# TEXAS_INSTRUMENTS_DRV8833.net
KiCad netlist of a schematic drawn in EAGLE
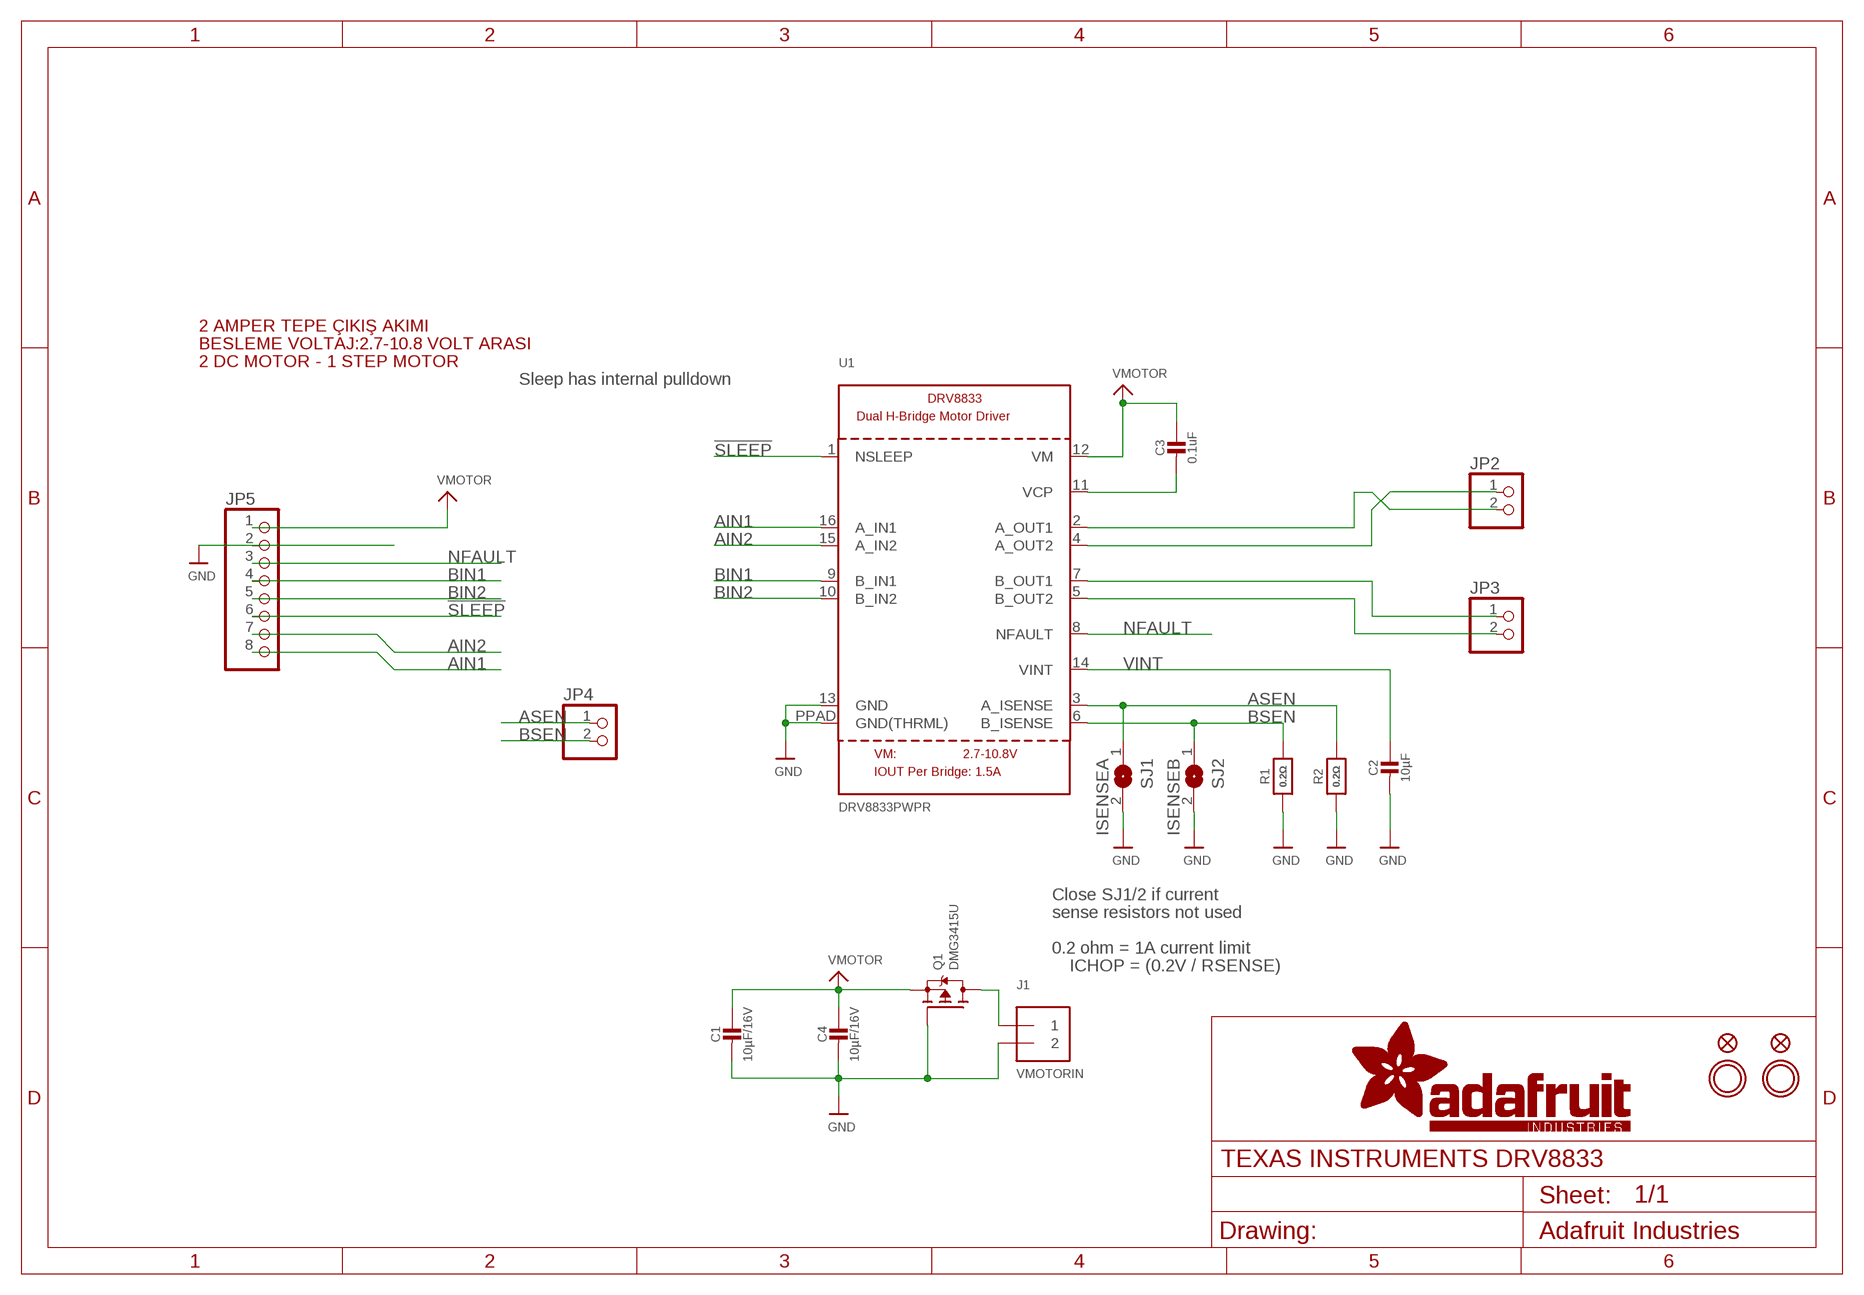
[diagram p0: schematic, sheet 1]

(export (version "E")
  (design (tool "Eeschema 10.0.6"))
  (components
    (comp (ref "C1")
      (value "10µF/16V")
      (footprint "eagle-import:0805-NO")
      (libsource (lib "eagle-import") (part "CAP_CERAMIC0805-NOOUTLINE"))
    )
    (comp (ref "C2")
      (value "10µF")
      (footprint "eagle-import:0805-NO")
      (libsource (lib "eagle-import") (part "CAP_CERAMIC0805-NOOUTLINE"))
    )
    (comp (ref "C3")
      (value "0.1uF")
      (footprint "eagle-import:0805-NO")
      (libsource (lib "eagle-import") (part "CAP_CERAMIC0805-NOOUTLINE"))
    )
    (comp (ref "C4")
      (value "10µF/16V")
      (footprint "eagle-import:0805-NO")
      (libsource (lib "eagle-import") (part "CAP_CERAMIC0805-NOOUTLINE"))
    )
    (comp (ref "FID1")
      (value "FIDUCIAL\"\"")
      (footprint "eagle-import:FIDUCIAL_1MM")
      (libsource (lib "eagle-import") (part "FIDUCIAL{dblquote}{dblquote}"))
    )
    (comp (ref "FID2")
      (value "FIDUCIAL\"\"")
      (footprint "eagle-import:FIDUCIAL_1MM")
      (libsource (lib "eagle-import") (part "FIDUCIAL{dblquote}{dblquote}"))
    )
    (comp (ref "J1")
      (value "VMOTORIN")
      (footprint "eagle-import:TERMBLOCK_1X2-3.5MM")
      (libsource (lib "eagle-import") (part "TERMBLOCK_1X2"))
    )
    (comp (ref "JP2")
      (value "HEADER-1X2ROUND")
      (footprint "eagle-import:1X02_ROUND")
      (libsource (lib "eagle-import") (part "HEADER-1X2ROUND"))
    )
    (comp (ref "JP3")
      (value "HEADER-1X2ROUND")
      (footprint "eagle-import:1X02_ROUND")
      (libsource (lib "eagle-import") (part "HEADER-1X2ROUND"))
    )
    (comp (ref "JP4")
      (value "HEADER-1X2ROUND")
      (footprint "eagle-import:1X02_ROUND")
      (libsource (lib "eagle-import") (part "HEADER-1X2ROUND"))
    )
    (comp (ref "JP5")
      (value "HEADER-1X870MIL")
      (footprint "eagle-import:1X08_ROUND_70")
      (libsource (lib "eagle-import") (part "HEADER-1X870MIL"))
    )
    (comp (ref "Q1")
      (value "DMG3415U")
      (footprint "eagle-import:SOT23-WIDE")
      (libsource (lib "eagle-import") (part "MOSFET-PWIDE"))
    )
    (comp (ref "R1")
      (value "0.2Ω")
      (footprint "eagle-import:_1206")
      (libsource (lib "eagle-import") (part "RESISTOR_1206"))
    )
    (comp (ref "R2")
      (value "0.2Ω")
      (footprint "eagle-import:_1206")
      (libsource (lib "eagle-import") (part "RESISTOR_1206"))
    )
    (comp (ref "SJ1")
      (value "ISENSEA")
      (footprint "eagle-import:SOLDERJUMPER_ARROW_NOPASTE")
      (libsource (lib "eagle-import") (part "SOLDERJUMPER"))
    )
    (comp (ref "SJ2")
      (value "ISENSEB")
      (footprint "eagle-import:SOLDERJUMPER_ARROW_NOPASTE")
      (libsource (lib "eagle-import") (part "SOLDERJUMPER"))
    )
    (comp (ref "U$13")
      (value "MOUNTINGHOLE2.5")
      (footprint "eagle-import:MOUNTINGHOLE_2.5_PLATED")
      (libsource (lib "eagle-import") (part "MOUNTINGHOLE2.5"))
    )
    (comp (ref "U$14")
      (value "MOUNTINGHOLE2.5")
      (footprint "eagle-import:MOUNTINGHOLE_2.5_PLATED")
      (libsource (lib "eagle-import") (part "MOUNTINGHOLE2.5"))
    )
    (comp (ref "U1")
      (value "DRV8833PWPR")
      (footprint "eagle-import:HTSSOP16")
      (libsource (lib "eagle-import") (part "DRV8833"))
    )
  )
  (nets
    (net (code "1") (name "/AIN1") (class "Default")
      (node (ref "JP5") (pin "8") (pinfunction "8_8") (pintype "passive"))
      (node (ref "U1") (pin "16") (pinfunction "A_IN1_16") (pintype "input"))
    )
    (net (code "2") (name "/AIN2") (class "Default")
      (node (ref "JP5") (pin "7") (pinfunction "7_7") (pintype "passive"))
      (node (ref "U1") (pin "15") (pinfunction "A_IN2_15") (pintype "input"))
    )
    (net (code "3") (name "/ASEN") (class "Default")
      (node (ref "JP4") (pin "1") (pinfunction "1_1") (pintype "passive"))
      (node (ref "R2") (pin "2") (pinfunction "2_2") (pintype "passive"))
      (node (ref "SJ1") (pin "1") (pinfunction "1_1") (pintype "passive"))
      (node (ref "U1") (pin "3") (pinfunction "A_ISENSE_3") (pintype "bidirectional"))
    )
    (net (code "4") (name "/BIN1") (class "Default")
      (node (ref "JP5") (pin "4") (pinfunction "4_4") (pintype "passive"))
      (node (ref "U1") (pin "9") (pinfunction "B_IN1_9") (pintype "input"))
    )
    (net (code "5") (name "/BIN2") (class "Default")
      (node (ref "JP5") (pin "5") (pinfunction "5_5") (pintype "passive"))
      (node (ref "U1") (pin "10") (pinfunction "B_IN2_10") (pintype "input"))
    )
    (net (code "6") (name "/BSEN") (class "Default")
      (node (ref "JP4") (pin "2") (pinfunction "2_2") (pintype "passive"))
      (node (ref "R1") (pin "2") (pinfunction "2_2") (pintype "passive"))
      (node (ref "SJ2") (pin "1") (pinfunction "1_1") (pintype "passive"))
      (node (ref "U1") (pin "6") (pinfunction "B_ISENSE_6") (pintype "bidirectional"))
    )
    (net (code "7") (name "/NFAULT") (class "Default")
      (node (ref "JP5") (pin "3") (pinfunction "3_3") (pintype "passive"))
      (node (ref "U1") (pin "8") (pinfunction "NFAULT_8") (pintype "bidirectional"))
    )
    (net (code "8") (name "/VINT") (class "Default")
      (node (ref "C2") (pin "1") (pinfunction "1_1") (pintype "passive"))
      (node (ref "U1") (pin "14") (pinfunction "VINT_14") (pintype "power_in"))
    )
    (net (code "9") (name "/~{SLEEP}") (class "Default")
      (node (ref "JP5") (pin "6") (pinfunction "6_6") (pintype "passive"))
      (node (ref "U1") (pin "1") (pinfunction "NSLEEP_1") (pintype "input"))
    )
    (net (code "10") (name "GND") (class "Default")
      (node (ref "C1") (pin "2") (pinfunction "2_2") (pintype "passive"))
      (node (ref "C2") (pin "2") (pinfunction "2_2") (pintype "passive"))
      (node (ref "C4") (pin "2") (pinfunction "2_2") (pintype "passive"))
      (node (ref "J1") (pin "2") (pinfunction "2_2") (pintype "passive"))
      (node (ref "JP5") (pin "2") (pinfunction "2_2") (pintype "passive"))
      (node (ref "Q1") (pin "1") (pinfunction "G_1") (pintype "passive"))
      (node (ref "R1") (pin "1") (pinfunction "1_1") (pintype "passive"))
      (node (ref "R2") (pin "1") (pinfunction "1_1") (pintype "passive"))
      (node (ref "SJ1") (pin "2") (pinfunction "2_2") (pintype "passive"))
      (node (ref "SJ2") (pin "2") (pinfunction "2_2") (pintype "passive"))
      (node (ref "U1") (pin "13") (pinfunction "GND_13") (pintype "power_in"))
      (node (ref "U1") (pin "PPAD") (pinfunction "GND(THRML)_PPAD") (pintype "power_in"))
    )
    (net (code "11") (name "Net-(Q1-D)") (class "Default")
      (node (ref "J1") (pin "1") (pinfunction "1_1") (pintype "passive"))
      (node (ref "Q1") (pin "3") (pinfunction "D_3") (pintype "passive"))
    )
    (net (code "12") (name "Net-(U1-A_OUT1)") (class "Default")
      (node (ref "JP2") (pin "2") (pinfunction "2_2") (pintype "passive"))
      (node (ref "U1") (pin "2") (pinfunction "A_OUT1_2") (pintype "output"))
    )
    (net (code "13") (name "Net-(U1-A_OUT2)") (class "Default")
      (node (ref "JP2") (pin "1") (pinfunction "1_1") (pintype "passive"))
      (node (ref "U1") (pin "4") (pinfunction "A_OUT2_4") (pintype "output"))
    )
    (net (code "14") (name "Net-(U1-B_OUT1)") (class "Default")
      (node (ref "JP3") (pin "1") (pinfunction "1_1") (pintype "passive"))
      (node (ref "U1") (pin "7") (pinfunction "B_OUT1_7") (pintype "output"))
    )
    (net (code "15") (name "Net-(U1-B_OUT2)") (class "Default")
      (node (ref "JP3") (pin "2") (pinfunction "2_2") (pintype "passive"))
      (node (ref "U1") (pin "5") (pinfunction "B_OUT2_5") (pintype "output"))
    )
    (net (code "16") (name "Net-(U1-VCP)") (class "Default")
      (node (ref "C3") (pin "2") (pinfunction "2_2") (pintype "passive"))
      (node (ref "U1") (pin "11") (pinfunction "VCP_11") (pintype "bidirectional"))
    )
    (net (code "17") (name "VMOTOR") (class "Default")
      (node (ref "C1") (pin "1") (pinfunction "1_1") (pintype "passive"))
      (node (ref "C3") (pin "1") (pinfunction "1_1") (pintype "passive"))
      (node (ref "C4") (pin "1") (pinfunction "1_1") (pintype "passive"))
      (node (ref "JP5") (pin "1") (pinfunction "1_1") (pintype "passive"))
      (node (ref "Q1") (pin "2") (pinfunction "S_2") (pintype "passive"))
      (node (ref "U1") (pin "12") (pinfunction "VM_12") (pintype "power_in"))
    )
  )
)
